# cpm_shield_basic.net
KiCad netlist of a schematic drawn in EAGLE
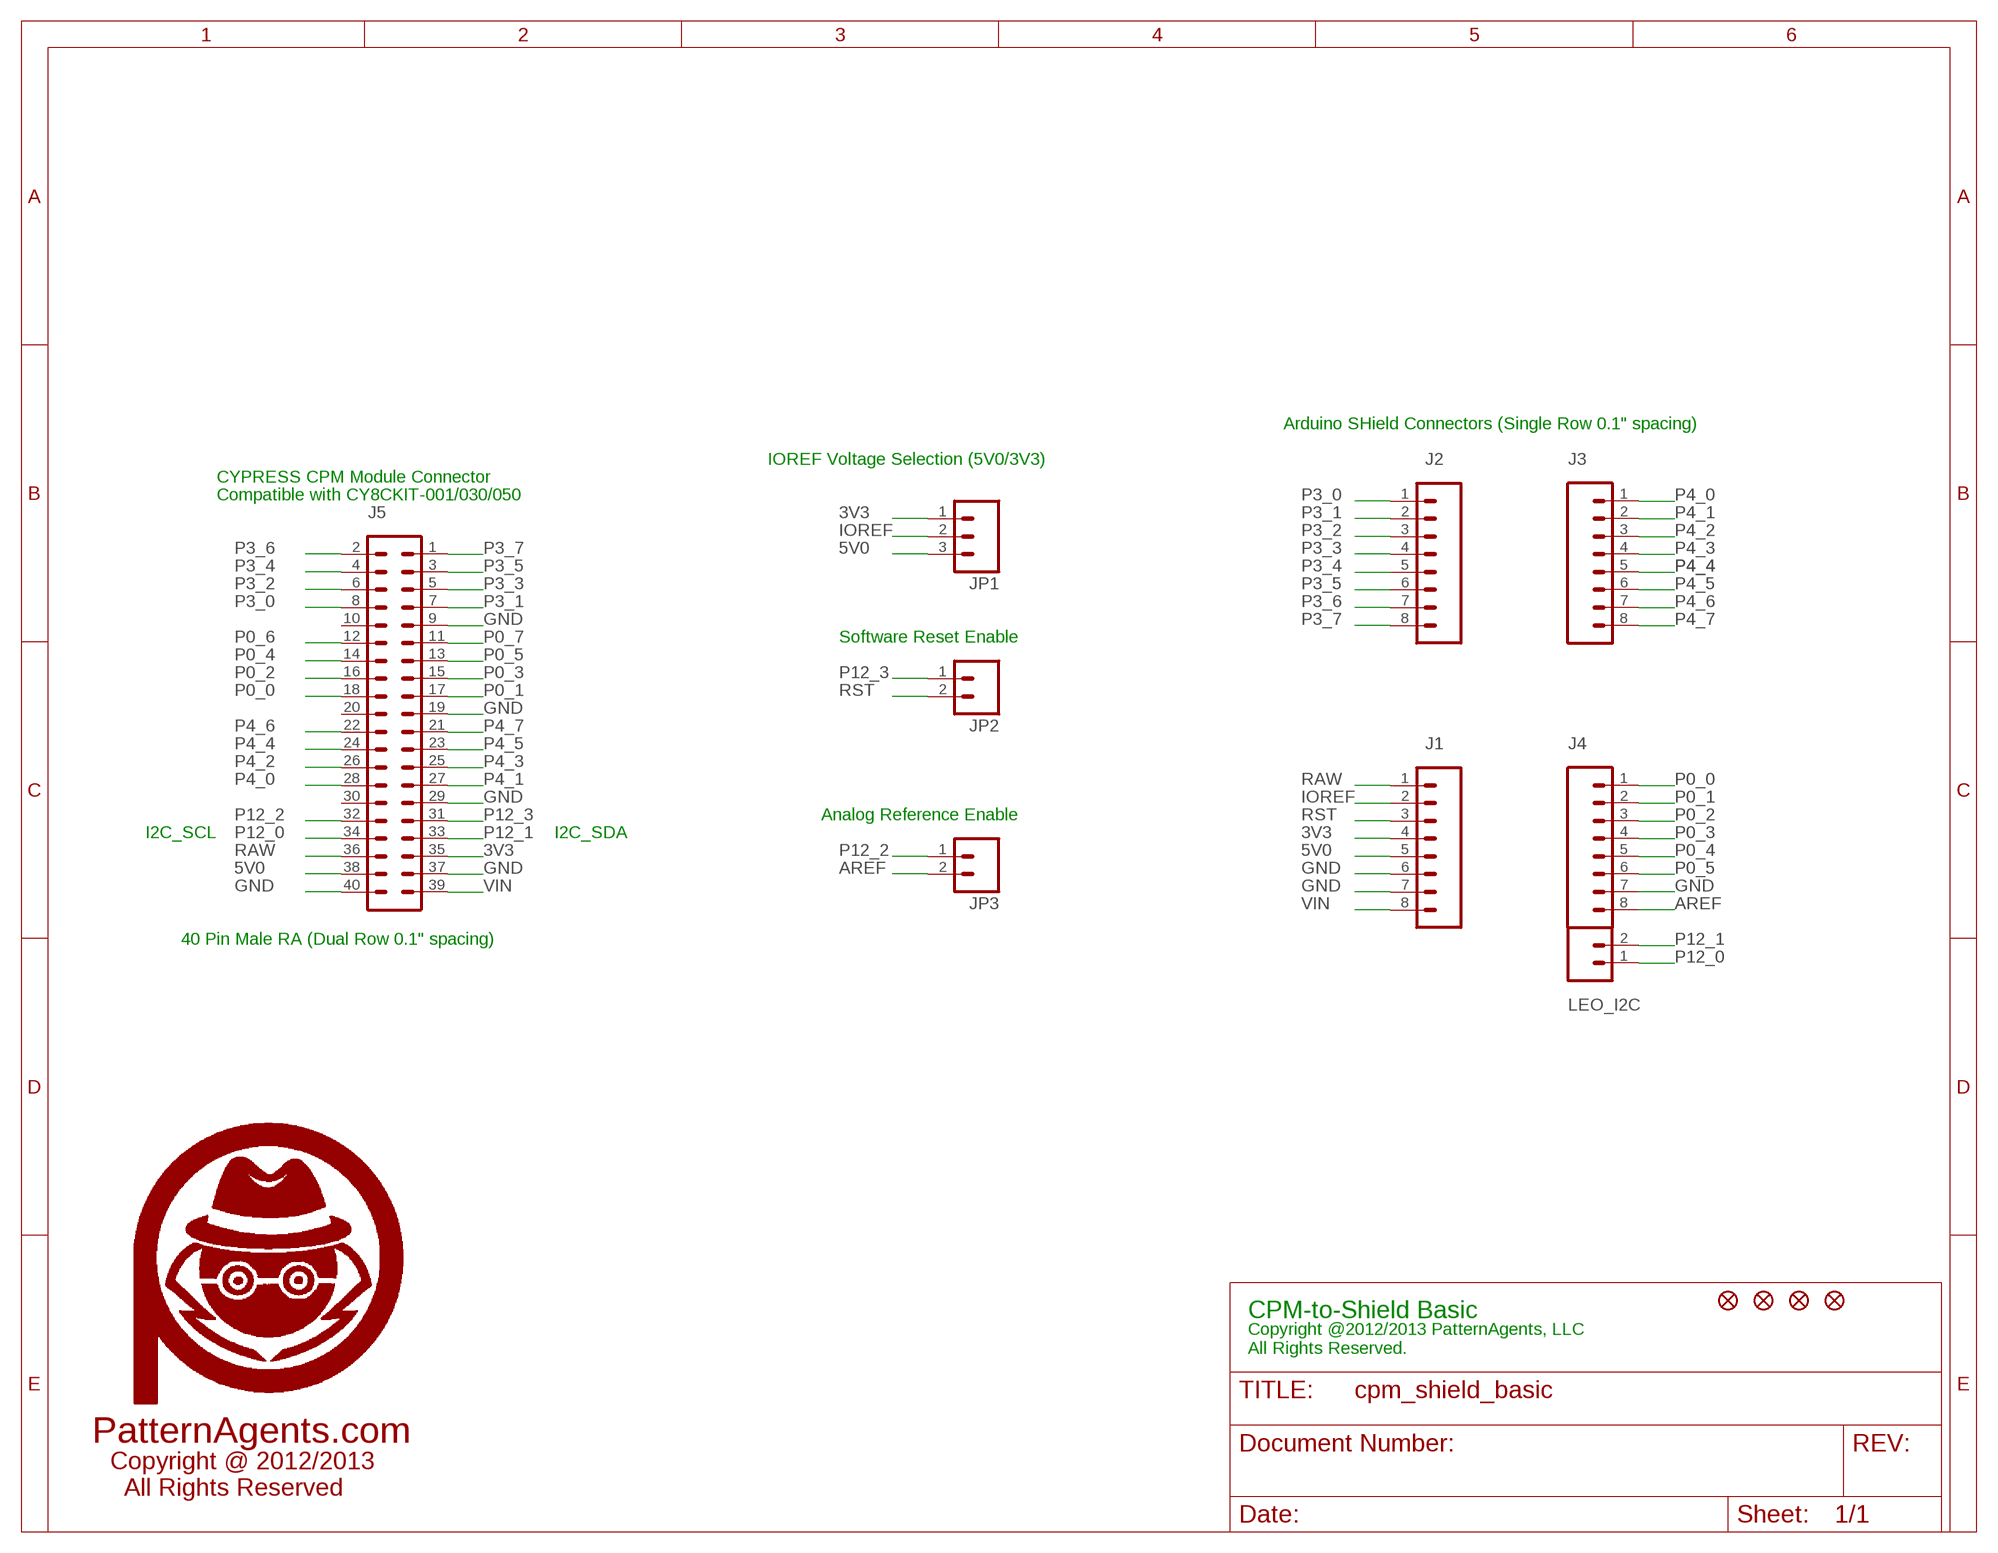
[diagram p0: schematic, sheet 1]

(export (version "E")
  (design (tool "Eeschema 10.0.6"))
  (components
    (comp (ref "J1")
      (value "SAMTEC")
      (footprint "eagle-import:1X08")
      (libsource (lib "eagle-import") (part "M081X08"))
    )
    (comp (ref "J2")
      (value "SAMTEC")
      (footprint "eagle-import:1X08")
      (libsource (lib "eagle-import") (part "M081X08"))
    )
    (comp (ref "J3")
      (value "SAMTEC")
      (footprint "eagle-import:1X08")
      (libsource (lib "eagle-import") (part "M081X08"))
    )
    (comp (ref "J4")
      (value "SAMTEC")
      (footprint "eagle-import:1X08")
      (libsource (lib "eagle-import") (part "M081X08"))
    )
    (comp (ref "J5")
      (value "SULLINS_SCS")
      (footprint "eagle-import:MA20-2")
      (fields (field (name "MF") "Sullins") (field (name "MPN") "PBC20DBAN"))
      (libsource (lib "eagle-import") (part "MA20-2"))
    )
    (comp (ref "JP1")
      (value "M03PS")
      (footprint "eagle-import:M03")
      (libsource (lib "eagle-import") (part "M03PS"))
    )
    (comp (ref "JP2")
      (value "M02PS")
      (footprint "eagle-import:MA02")
      (libsource (lib "eagle-import") (part "M02PS"))
    )
    (comp (ref "JP3")
      (value "M02PS")
      (footprint "eagle-import:MA02")
      (libsource (lib "eagle-import") (part "M02PS"))
    )
    (comp (ref "JP4")
      (value "FIDUCIAL1.5X3")
      (footprint "eagle-import:FIDUCIAL-1.5X3")
      (libsource (lib "eagle-import") (part "FIDUCIAL1.5X3"))
    )
    (comp (ref "JP5")
      (value "FIDUCIAL1.5X3")
      (footprint "eagle-import:FIDUCIAL-1.5X3")
      (libsource (lib "eagle-import") (part "FIDUCIAL1.5X3"))
    )
    (comp (ref "JP6")
      (value "FIDUCIAL1.5X3")
      (footprint "eagle-import:FIDUCIAL-1.5X3")
      (libsource (lib "eagle-import") (part "FIDUCIAL1.5X3"))
    )
    (comp (ref "JP7")
      (value "FIDUCIAL1.5X3")
      (footprint "eagle-import:FIDUCIAL-1.5X3")
      (libsource (lib "eagle-import") (part "FIDUCIAL1.5X3"))
    )
    (comp (ref "LEO_I2C")
      (value "M02PS")
      (footprint "eagle-import:MA02")
      (libsource (lib "eagle-import") (part "M02PS"))
    )
    (comp (ref "U$3")
      (value "LOGO_PA_AGENTLARGE")
      (footprint "eagle-import:LOGO_PA_AGENT_LARGE")
      (libsource (lib "eagle-import") (part "LOGO_PA_AGENTLARGE"))
    )
  )
  (nets
    (net (code "1") (name "/3V3") (class "Default")
      (node (ref "J1") (pin "4") (pinfunction "4_4") (pintype "passive"))
      (node (ref "J5") (pin "35") (pinfunction "35_35") (pintype "passive"))
      (node (ref "JP1") (pin "1") (pinfunction "1_1") (pintype "passive"))
    )
    (net (code "2") (name "/5V0") (class "Default")
      (node (ref "J1") (pin "5") (pinfunction "5_5") (pintype "passive"))
      (node (ref "J5") (pin "38") (pinfunction "38_38") (pintype "passive"))
      (node (ref "JP1") (pin "3") (pinfunction "3_3") (pintype "passive"))
    )
    (net (code "3") (name "/AREF") (class "Default")
      (node (ref "J4") (pin "8") (pinfunction "8_8") (pintype "passive"))
      (node (ref "JP3") (pin "2") (pinfunction "2_2") (pintype "passive"))
    )
    (net (code "4") (name "/GND") (class "Default")
      (node (ref "J1") (pin "6") (pinfunction "6_6") (pintype "passive"))
      (node (ref "J1") (pin "7") (pinfunction "7_7") (pintype "passive"))
      (node (ref "J4") (pin "7") (pinfunction "7_7") (pintype "passive"))
      (node (ref "J5") (pin "19") (pinfunction "19_19") (pintype "passive"))
      (node (ref "J5") (pin "29") (pinfunction "29_29") (pintype "passive"))
      (node (ref "J5") (pin "37") (pinfunction "37_37") (pintype "passive"))
      (node (ref "J5") (pin "40") (pinfunction "40_40") (pintype "passive"))
      (node (ref "J5") (pin "9") (pinfunction "9_9") (pintype "passive"))
    )
    (net (code "5") (name "/IOREF") (class "Default")
      (node (ref "J1") (pin "2") (pinfunction "2_2") (pintype "passive"))
      (node (ref "JP1") (pin "2") (pinfunction "2_2") (pintype "passive"))
    )
    (net (code "6") (name "/P0_0") (class "Default")
      (node (ref "J4") (pin "1") (pinfunction "1_1") (pintype "passive"))
      (node (ref "J5") (pin "18") (pinfunction "18_18") (pintype "passive"))
    )
    (net (code "7") (name "/P0_1") (class "Default")
      (node (ref "J4") (pin "2") (pinfunction "2_2") (pintype "passive"))
      (node (ref "J5") (pin "17") (pinfunction "17_17") (pintype "passive"))
    )
    (net (code "8") (name "/P0_2") (class "Default")
      (node (ref "J4") (pin "3") (pinfunction "3_3") (pintype "passive"))
      (node (ref "J5") (pin "16") (pinfunction "16_16") (pintype "passive"))
    )
    (net (code "9") (name "/P0_3") (class "Default")
      (node (ref "J4") (pin "4") (pinfunction "4_4") (pintype "passive"))
      (node (ref "J5") (pin "15") (pinfunction "15_15") (pintype "passive"))
    )
    (net (code "10") (name "/P0_4") (class "Default")
      (node (ref "J4") (pin "5") (pinfunction "5_5") (pintype "passive"))
      (node (ref "J5") (pin "14") (pinfunction "14_14") (pintype "passive"))
    )
    (net (code "11") (name "/P0_5") (class "Default")
      (node (ref "J4") (pin "6") (pinfunction "6_6") (pintype "passive"))
      (node (ref "J5") (pin "13") (pinfunction "13_13") (pintype "passive"))
    )
    (net (code "12") (name "/P0_6") (class "Default")
      (node (ref "J5") (pin "12") (pinfunction "12_12") (pintype "passive"))
    )
    (net (code "13") (name "/P0_7") (class "Default")
      (node (ref "J5") (pin "11") (pinfunction "11_11") (pintype "passive"))
    )
    (net (code "14") (name "/P3_0") (class "Default")
      (node (ref "J2") (pin "1") (pinfunction "1_1") (pintype "passive"))
      (node (ref "J5") (pin "8") (pinfunction "8_8") (pintype "passive"))
    )
    (net (code "15") (name "/P3_1") (class "Default")
      (node (ref "J2") (pin "2") (pinfunction "2_2") (pintype "passive"))
      (node (ref "J5") (pin "7") (pinfunction "7_7") (pintype "passive"))
    )
    (net (code "16") (name "/P3_2") (class "Default")
      (node (ref "J2") (pin "3") (pinfunction "3_3") (pintype "passive"))
      (node (ref "J5") (pin "6") (pinfunction "6_6") (pintype "passive"))
    )
    (net (code "17") (name "/P3_3") (class "Default")
      (node (ref "J2") (pin "4") (pinfunction "4_4") (pintype "passive"))
      (node (ref "J5") (pin "5") (pinfunction "5_5") (pintype "passive"))
    )
    (net (code "18") (name "/P3_4") (class "Default")
      (node (ref "J2") (pin "5") (pinfunction "5_5") (pintype "passive"))
      (node (ref "J5") (pin "4") (pinfunction "4_4") (pintype "passive"))
    )
    (net (code "19") (name "/P3_5") (class "Default")
      (node (ref "J2") (pin "6") (pinfunction "6_6") (pintype "passive"))
      (node (ref "J5") (pin "3") (pinfunction "3_3") (pintype "passive"))
    )
    (net (code "20") (name "/P3_6") (class "Default")
      (node (ref "J2") (pin "7") (pinfunction "7_7") (pintype "passive"))
      (node (ref "J5") (pin "2") (pinfunction "2_2") (pintype "passive"))
    )
    (net (code "21") (name "/P3_7") (class "Default")
      (node (ref "J2") (pin "8") (pinfunction "8_8") (pintype "passive"))
      (node (ref "J5") (pin "1") (pinfunction "1_1") (pintype "passive"))
    )
    (net (code "22") (name "/P4_0") (class "Default")
      (node (ref "J3") (pin "1") (pinfunction "1_1") (pintype "passive"))
      (node (ref "J5") (pin "28") (pinfunction "28_28") (pintype "passive"))
    )
    (net (code "23") (name "/P4_1") (class "Default")
      (node (ref "J3") (pin "2") (pinfunction "2_2") (pintype "passive"))
      (node (ref "J5") (pin "27") (pinfunction "27_27") (pintype "passive"))
    )
    (net (code "24") (name "/P4_2") (class "Default")
      (node (ref "J3") (pin "3") (pinfunction "3_3") (pintype "passive"))
      (node (ref "J5") (pin "26") (pinfunction "26_26") (pintype "passive"))
    )
    (net (code "25") (name "/P4_3") (class "Default")
      (node (ref "J3") (pin "4") (pinfunction "4_4") (pintype "passive"))
      (node (ref "J5") (pin "25") (pinfunction "25_25") (pintype "passive"))
    )
    (net (code "26") (name "/P4_4") (class "Default")
      (node (ref "J3") (pin "5") (pinfunction "5_5") (pintype "passive"))
      (node (ref "J5") (pin "24") (pinfunction "24_24") (pintype "passive"))
    )
    (net (code "27") (name "/P4_5") (class "Default")
      (node (ref "J3") (pin "6") (pinfunction "6_6") (pintype "passive"))
      (node (ref "J5") (pin "23") (pinfunction "23_23") (pintype "passive"))
    )
    (net (code "28") (name "/P4_6") (class "Default")
      (node (ref "J3") (pin "7") (pinfunction "7_7") (pintype "passive"))
      (node (ref "J5") (pin "22") (pinfunction "22_22") (pintype "passive"))
    )
    (net (code "29") (name "/P4_7") (class "Default")
      (node (ref "J3") (pin "8") (pinfunction "8_8") (pintype "passive"))
      (node (ref "J5") (pin "21") (pinfunction "21_21") (pintype "passive"))
    )
    (net (code "30") (name "/P12_0") (class "Default")
      (node (ref "J5") (pin "34") (pinfunction "34_34") (pintype "passive"))
      (node (ref "LEO_I2C") (pin "1") (pinfunction "1_1") (pintype "passive"))
    )
    (net (code "31") (name "/P12_1") (class "Default")
      (node (ref "J5") (pin "33") (pinfunction "33_33") (pintype "passive"))
      (node (ref "LEO_I2C") (pin "2") (pinfunction "2_2") (pintype "passive"))
    )
    (net (code "32") (name "/P12_2") (class "Default")
      (node (ref "J5") (pin "32") (pinfunction "32_32") (pintype "passive"))
      (node (ref "JP3") (pin "1") (pinfunction "1_1") (pintype "passive"))
    )
    (net (code "33") (name "/P12_3") (class "Default")
      (node (ref "J5") (pin "31") (pinfunction "31_31") (pintype "passive"))
      (node (ref "JP2") (pin "1") (pinfunction "1_1") (pintype "passive"))
    )
    (net (code "34") (name "/RAW") (class "Default")
      (node (ref "J1") (pin "1") (pinfunction "1_1") (pintype "passive"))
      (node (ref "J5") (pin "36") (pinfunction "36_36") (pintype "passive"))
    )
    (net (code "35") (name "/RST") (class "Default")
      (node (ref "J1") (pin "3") (pinfunction "3_3") (pintype "passive"))
      (node (ref "JP2") (pin "2") (pinfunction "2_2") (pintype "passive"))
    )
    (net (code "36") (name "/VIN") (class "Default")
      (node (ref "J1") (pin "8") (pinfunction "8_8") (pintype "passive"))
      (node (ref "J5") (pin "39") (pinfunction "39_39") (pintype "passive"))
    )
    (net (code "37") (name "unconnected-(J5-Pad10)") (class "Default")
      (node (ref "J5") (pin "10") (pinfunction "10_10") (pintype "passive"))
    )
    (net (code "38") (name "unconnected-(J5-Pad20)") (class "Default")
      (node (ref "J5") (pin "20") (pinfunction "20_20") (pintype "passive"))
    )
    (net (code "39") (name "unconnected-(J5-Pad30)") (class "Default")
      (node (ref "J5") (pin "30") (pinfunction "30_30") (pintype "passive"))
    )
  )
)
